# termostato.net
KiCad netlist of a schematic drawn in EAGLE
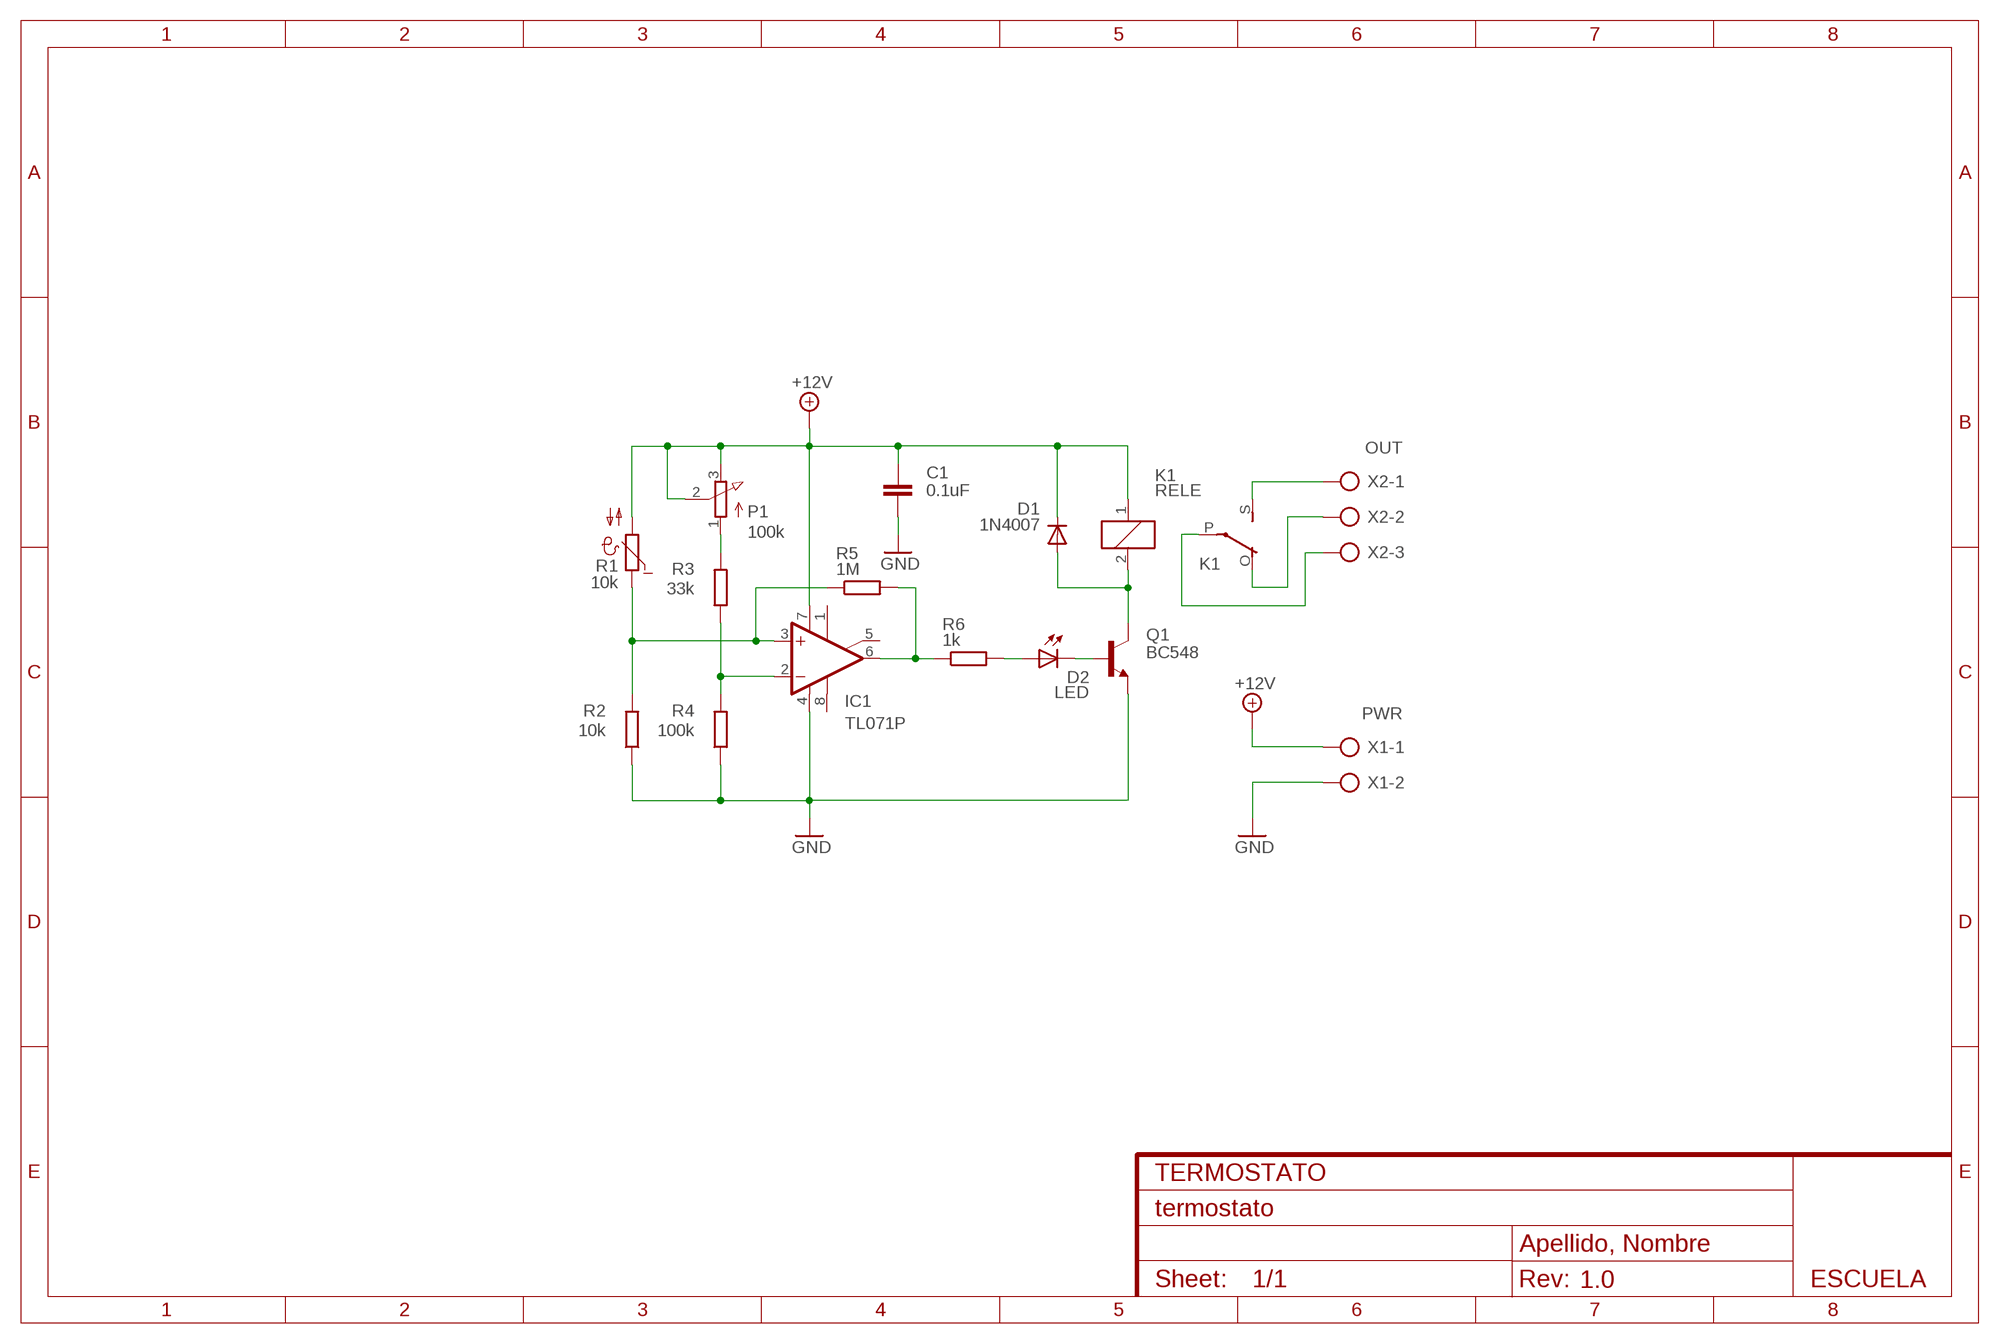
[diagram p0: schematic, sheet 1]

(export (version "E")
  (design (tool "Eeschema 10.0.6"))
  (components
    (comp (ref "C1")
      (value "0.1uF")
      (footprint "eagle-import:C025_050-025X075")
      (libsource (lib "eagle-import") (part "C-EU025_050-025X075"))
    )
    (comp (ref "D1")
      (value "1N4007")
      (footprint "eagle-import:DO41-10")
      (libsource (lib "eagle-import") (part "1N4007"))
    )
    (comp (ref "D2")
      (value "LED")
      (footprint "eagle-import:LED_3MM")
      (libsource (lib "eagle-import") (part "LED3MM"))
    )
    (comp (ref "IC1")
      (value "TL071P")
      (footprint "eagle-import:DIL08")
      (libsource (lib "eagle-import") (part "TL071P"))
    )
    (comp (ref "K1")
      (value "RELE")
      (footprint "eagle-import:G5LE")
      (libsource (lib "eagle-import") (part "RELE_G5LE"))
    )
    (comp (ref "P1")
      (value "100k")
      (footprint "eagle-import:3RP_1610N")
      (libsource (lib "eagle-import") (part "3RP/1610N"))
    )
    (comp (ref "Q1")
      (value "BC548")
      (footprint "eagle-import:TO92-EBC")
      (libsource (lib "eagle-import") (part "BC548"))
    )
    (comp (ref "R1")
      (value "10k")
      (footprint "eagle-import:P642")
      (libsource (lib "eagle-import") (part "NTC642-6"))
    )
    (comp (ref "R2")
      (value "10k")
      (footprint "eagle-import:0204_7")
      (libsource (lib "eagle-import") (part "RESISTOR-EU0204/7"))
    )
    (comp (ref "R3")
      (value "33k")
      (footprint "eagle-import:0204_7")
      (libsource (lib "eagle-import") (part "RESISTOR-EU0204/7"))
    )
    (comp (ref "R4")
      (value "100k")
      (footprint "eagle-import:0204_7")
      (libsource (lib "eagle-import") (part "RESISTOR-EU0204/7"))
    )
    (comp (ref "R5")
      (value "1M")
      (footprint "eagle-import:0204_7")
      (libsource (lib "eagle-import") (part "RESISTOR-EU0204/7"))
    )
    (comp (ref "R6")
      (value "1k")
      (footprint "eagle-import:0204_7")
      (libsource (lib "eagle-import") (part "RESISTOR-EU0204/7"))
    )
    (comp (ref "X1")
      (value "PWR")
      (footprint "eagle-import:AK500_2")
      (libsource (lib "eagle-import") (part "BORNERA_AK500/2"))
    )
    (comp (ref "X2")
      (value "OUT")
      (footprint "eagle-import:AK500_3")
      (libsource (lib "eagle-import") (part "BORNERA_AK500/3"))
    )
  )
  (nets
    (net (code "1") (name "+12V") (class "Default")
      (node (ref "C1") (pin "1") (pinfunction "1_1") (pintype "passive"))
      (node (ref "D1") (pin "C") (pinfunction "C_C") (pintype "passive"))
      (node (ref "IC1") (pin "7") (pinfunction "V+_7") (pintype "power_in"))
      (node (ref "K1") (pin "1") (pinfunction "1_1") (pintype "passive"))
      (node (ref "P1") (pin "2") (pinfunction "S_2") (pintype "passive"))
      (node (ref "P1") (pin "3") (pinfunction "E_3") (pintype "passive"))
      (node (ref "R1") (pin "2") (pinfunction "2_2") (pintype "passive"))
      (node (ref "X1") (pin "1") (pinfunction "KL_1") (pintype "passive"))
    )
    (net (code "2") (name "GND") (class "Default")
      (node (ref "C1") (pin "2") (pinfunction "2_2") (pintype "passive"))
      (node (ref "IC1") (pin "4") (pinfunction "V-_4") (pintype "power_in"))
      (node (ref "Q1") (pin "E") (pinfunction "E_E") (pintype "passive"))
      (node (ref "R2") (pin "1") (pinfunction "1_1") (pintype "passive"))
      (node (ref "R4") (pin "1") (pinfunction "1_1") (pintype "passive"))
      (node (ref "X1") (pin "2") (pinfunction "KL_2") (pintype "passive"))
    )
    (net (code "3") (name "Net-(D1-PadA)") (class "Default")
      (node (ref "D1") (pin "A") (pinfunction "A_A") (pintype "passive"))
      (node (ref "K1") (pin "2") (pinfunction "2_2") (pintype "passive"))
      (node (ref "Q1") (pin "C") (pinfunction "C_C") (pintype "passive"))
    )
    (net (code "4") (name "Net-(D2-C)") (class "Default")
      (node (ref "D2") (pin "K") (pinfunction "C_K") (pintype "passive"))
      (node (ref "Q1") (pin "B") (pinfunction "B_B") (pintype "passive"))
    )
    (net (code "5") (name "Net-(D2-PadA)") (class "Default")
      (node (ref "D2") (pin "A") (pinfunction "A_A") (pintype "passive"))
      (node (ref "R6") (pin "2") (pinfunction "2_2") (pintype "passive"))
    )
    (net (code "6") (name "Net-(IC1-+IN)") (class "Default")
      (node (ref "IC1") (pin "3") (pinfunction "+IN_3") (pintype "input"))
      (node (ref "R1") (pin "1") (pinfunction "1_1") (pintype "passive"))
      (node (ref "R2") (pin "2") (pinfunction "2_2") (pintype "passive"))
      (node (ref "R5") (pin "1") (pinfunction "1_1") (pintype "passive"))
    )
    (net (code "7") (name "Net-(IC1--IN)") (class "Default")
      (node (ref "IC1") (pin "2") (pinfunction "-IN_2") (pintype "input"))
      (node (ref "R3") (pin "1") (pinfunction "1_1") (pintype "passive"))
      (node (ref "R4") (pin "2") (pinfunction "2_2") (pintype "passive"))
    )
    (net (code "8") (name "Net-(IC1-OUT)") (class "Default")
      (node (ref "IC1") (pin "6") (pinfunction "OUT_6") (pintype "output"))
      (node (ref "R5") (pin "2") (pinfunction "2_2") (pintype "passive"))
      (node (ref "R6") (pin "1") (pinfunction "1_1") (pintype "passive"))
    )
    (net (code "9") (name "Net-(K1B-COM)") (class "Default")
      (node (ref "K1") (pin "P") (pinfunction "COM_P") (pintype "passive"))
      (node (ref "X2") (pin "3") (pinfunction "KL_3") (pintype "passive"))
    )
    (net (code "10") (name "Net-(K1B-NA)") (class "Default")
      (node (ref "K1") (pin "S") (pinfunction "NA_S") (pintype "passive"))
      (node (ref "X2") (pin "1") (pinfunction "KL_1") (pintype "passive"))
    )
    (net (code "11") (name "Net-(K1B-NC)") (class "Default")
      (node (ref "K1") (pin "O") (pinfunction "NC_O") (pintype "passive"))
      (node (ref "X2") (pin "2") (pinfunction "KL_2") (pintype "passive"))
    )
    (net (code "12") (name "Net-(P1-A)") (class "Default")
      (node (ref "P1") (pin "1") (pinfunction "A_1") (pintype "passive"))
      (node (ref "R3") (pin "2") (pinfunction "2_2") (pintype "passive"))
    )
    (net (code "13") (name "unconnected-(IC1-ON1-Pad1)") (class "Default")
      (node (ref "IC1") (pin "1") (pinfunction "ON1_1") (pintype "passive"))
    )
    (net (code "14") (name "unconnected-(IC1-ON2-Pad5)") (class "Default")
      (node (ref "IC1") (pin "5") (pinfunction "ON2_5") (pintype "passive"))
    )
    (net (code "15") (name "unconnected-(IC1-OPT-Pad8)") (class "Default")
      (node (ref "IC1") (pin "8") (pinfunction "OPT_8") (pintype "passive"))
    )
  )
)
